# Multiplexer_Circuits.net
KiCad netlist of a schematic drawn in EAGLE
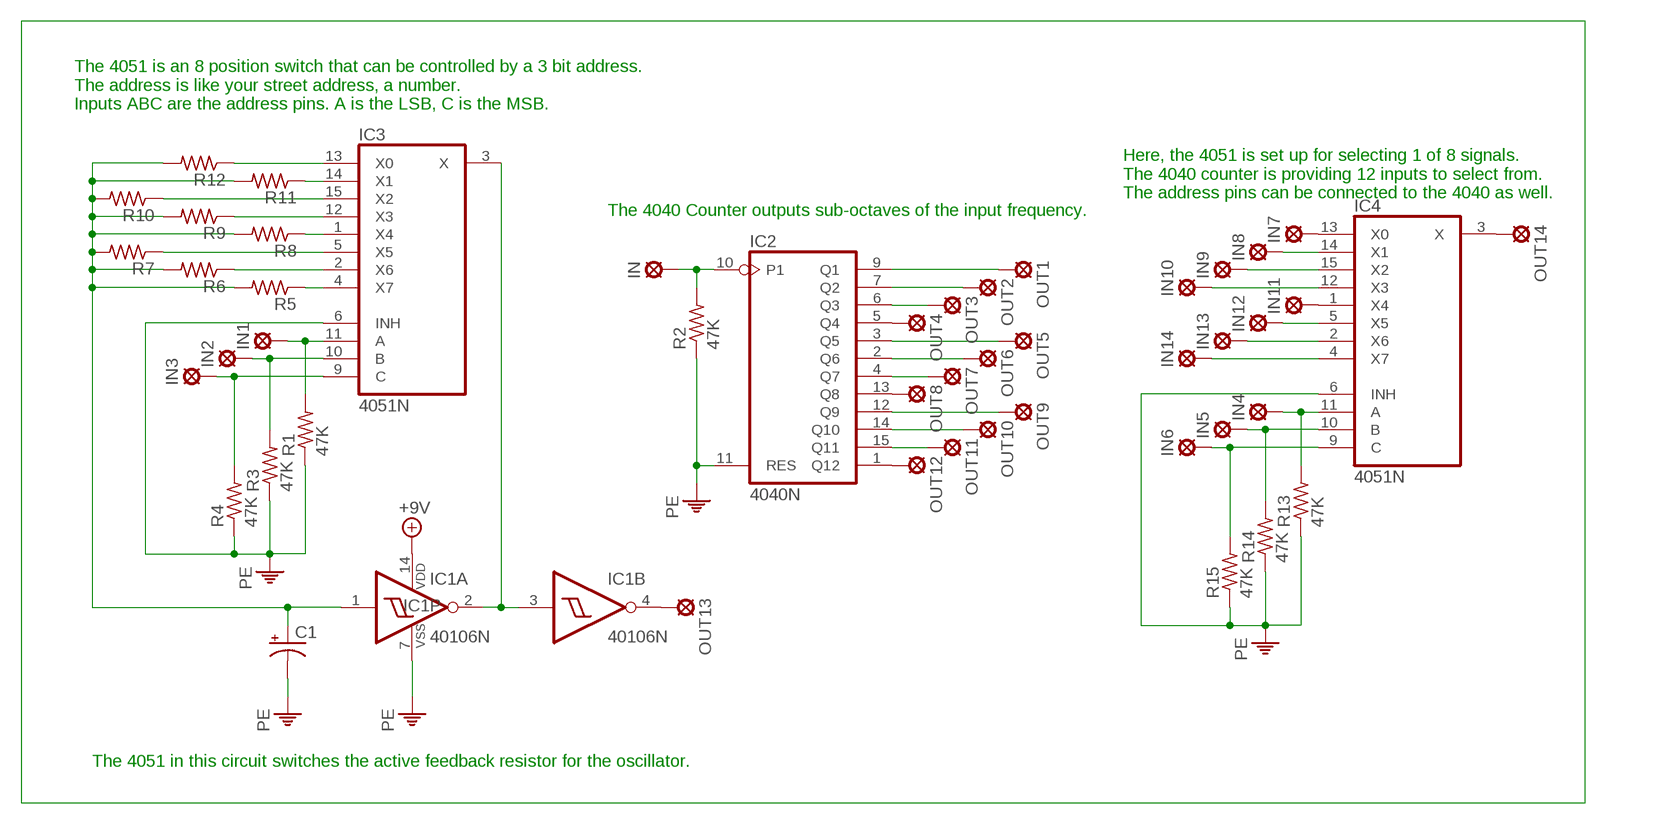
[diagram p0: schematic, sheet 1]

(export (version "E")
  (design (tool "Eeschema 10.0.6"))
  (components
    (comp (ref "C1")
      (value "CPOL-USE2,5-6E")
      (footprint "eagle-import:E2,5-6E")
      (libsource (lib "eagle-import") (part "CPOL-USE2,5-6E"))
    )
    (comp (ref "IC1")
      (value "40106N")
      (footprint "eagle-import:DIL14")
      (libsource (lib "eagle-import") (part "40106N"))
    )
    (comp (ref "IC2")
      (value "4040N")
      (footprint "eagle-import:DIL16")
      (libsource (lib "eagle-import") (part "4040N"))
    )
    (comp (ref "IC3")
      (value "4051N")
      (footprint "eagle-import:DIL16")
      (libsource (lib "eagle-import") (part "4051N"))
    )
    (comp (ref "IC4")
      (value "4051N")
      (footprint "eagle-import:DIL16")
      (libsource (lib "eagle-import") (part "4051N"))
    )
    (comp (ref "IN")
      (value "MCS10B")
      (footprint "eagle-import:MCS10B")
      (libsource (lib "eagle-import") (part "MCS10B"))
    )
    (comp (ref "IN1")
      (value "MCS10B")
      (footprint "eagle-import:MCS10B")
      (libsource (lib "eagle-import") (part "MCS10B"))
    )
    (comp (ref "IN2")
      (value "MCS10B")
      (footprint "eagle-import:MCS10B")
      (libsource (lib "eagle-import") (part "MCS10B"))
    )
    (comp (ref "IN3")
      (value "MCS10B")
      (footprint "eagle-import:MCS10B")
      (libsource (lib "eagle-import") (part "MCS10B"))
    )
    (comp (ref "IN4")
      (value "MCS10B")
      (footprint "eagle-import:MCS10B")
      (libsource (lib "eagle-import") (part "MCS10B"))
    )
    (comp (ref "IN5")
      (value "MCS10B")
      (footprint "eagle-import:MCS10B")
      (libsource (lib "eagle-import") (part "MCS10B"))
    )
    (comp (ref "IN6")
      (value "MCS10B")
      (footprint "eagle-import:MCS10B")
      (libsource (lib "eagle-import") (part "MCS10B"))
    )
    (comp (ref "IN7")
      (value "MCS10B")
      (footprint "eagle-import:MCS10B")
      (libsource (lib "eagle-import") (part "MCS10B"))
    )
    (comp (ref "IN8")
      (value "MCS10B")
      (footprint "eagle-import:MCS10B")
      (libsource (lib "eagle-import") (part "MCS10B"))
    )
    (comp (ref "IN9")
      (value "MCS10B")
      (footprint "eagle-import:MCS10B")
      (libsource (lib "eagle-import") (part "MCS10B"))
    )
    (comp (ref "IN10")
      (value "MCS10B")
      (footprint "eagle-import:MCS10B")
      (libsource (lib "eagle-import") (part "MCS10B"))
    )
    (comp (ref "IN11")
      (value "MCS10B")
      (footprint "eagle-import:MCS10B")
      (libsource (lib "eagle-import") (part "MCS10B"))
    )
    (comp (ref "IN12")
      (value "MCS10B")
      (footprint "eagle-import:MCS10B")
      (libsource (lib "eagle-import") (part "MCS10B"))
    )
    (comp (ref "IN13")
      (value "MCS10B")
      (footprint "eagle-import:MCS10B")
      (libsource (lib "eagle-import") (part "MCS10B"))
    )
    (comp (ref "IN14")
      (value "MCS10B")
      (footprint "eagle-import:MCS10B")
      (libsource (lib "eagle-import") (part "MCS10B"))
    )
    (comp (ref "OUT1")
      (value "MCS10B")
      (footprint "eagle-import:MCS10B")
      (libsource (lib "eagle-import") (part "MCS10B"))
    )
    (comp (ref "OUT2")
      (value "MCS10B")
      (footprint "eagle-import:MCS10B")
      (libsource (lib "eagle-import") (part "MCS10B"))
    )
    (comp (ref "OUT3")
      (value "MCS10B")
      (footprint "eagle-import:MCS10B")
      (libsource (lib "eagle-import") (part "MCS10B"))
    )
    (comp (ref "OUT4")
      (value "MCS10B")
      (footprint "eagle-import:MCS10B")
      (libsource (lib "eagle-import") (part "MCS10B"))
    )
    (comp (ref "OUT5")
      (value "MCS10B")
      (footprint "eagle-import:MCS10B")
      (libsource (lib "eagle-import") (part "MCS10B"))
    )
    (comp (ref "OUT6")
      (value "MCS10B")
      (footprint "eagle-import:MCS10B")
      (libsource (lib "eagle-import") (part "MCS10B"))
    )
    (comp (ref "OUT7")
      (value "MCS10B")
      (footprint "eagle-import:MCS10B")
      (libsource (lib "eagle-import") (part "MCS10B"))
    )
    (comp (ref "OUT8")
      (value "MCS10B")
      (footprint "eagle-import:MCS10B")
      (libsource (lib "eagle-import") (part "MCS10B"))
    )
    (comp (ref "OUT9")
      (value "MCS10B")
      (footprint "eagle-import:MCS10B")
      (libsource (lib "eagle-import") (part "MCS10B"))
    )
    (comp (ref "OUT10")
      (value "MCS10B")
      (footprint "eagle-import:MCS10B")
      (libsource (lib "eagle-import") (part "MCS10B"))
    )
    (comp (ref "OUT11")
      (value "MCS10B")
      (footprint "eagle-import:MCS10B")
      (libsource (lib "eagle-import") (part "MCS10B"))
    )
    (comp (ref "OUT12")
      (value "MCS10B")
      (footprint "eagle-import:MCS10B")
      (libsource (lib "eagle-import") (part "MCS10B"))
    )
    (comp (ref "OUT13")
      (value "MCS10B")
      (footprint "eagle-import:MCS10B")
      (libsource (lib "eagle-import") (part "MCS10B"))
    )
    (comp (ref "OUT14")
      (value "MCS10B")
      (footprint "eagle-import:MCS10B")
      (libsource (lib "eagle-import") (part "MCS10B"))
    )
    (comp (ref "R1")
      (value "47K")
      (footprint "eagle-import:0204_7")
      (libsource (lib "eagle-import") (part "R-US_0204/7"))
    )
    (comp (ref "R2")
      (value "47K")
      (footprint "eagle-import:0204_7")
      (libsource (lib "eagle-import") (part "R-US_0204/7"))
    )
    (comp (ref "R3")
      (value "47K")
      (footprint "eagle-import:0204_7")
      (libsource (lib "eagle-import") (part "R-US_0204/7"))
    )
    (comp (ref "R4")
      (value "47K")
      (footprint "eagle-import:0204_7")
      (libsource (lib "eagle-import") (part "R-US_0204/7"))
    )
    (comp (ref "R5")
      (value "R-US_0204/7")
      (footprint "eagle-import:0204_7")
      (libsource (lib "eagle-import") (part "R-US_0204/7"))
    )
    (comp (ref "R6")
      (value "R-US_0204/7")
      (footprint "eagle-import:0204_7")
      (libsource (lib "eagle-import") (part "R-US_0204/7"))
    )
    (comp (ref "R7")
      (value "R-US_0204/7")
      (footprint "eagle-import:0204_7")
      (libsource (lib "eagle-import") (part "R-US_0204/7"))
    )
    (comp (ref "R8")
      (value "R-US_0204/7")
      (footprint "eagle-import:0204_7")
      (libsource (lib "eagle-import") (part "R-US_0204/7"))
    )
    (comp (ref "R9")
      (value "R-US_0204/7")
      (footprint "eagle-import:0204_7")
      (libsource (lib "eagle-import") (part "R-US_0204/7"))
    )
    (comp (ref "R10")
      (value "R-US_0204/7")
      (footprint "eagle-import:0204_7")
      (libsource (lib "eagle-import") (part "R-US_0204/7"))
    )
    (comp (ref "R11")
      (value "R-US_0204/7")
      (footprint "eagle-import:0204_7")
      (libsource (lib "eagle-import") (part "R-US_0204/7"))
    )
    (comp (ref "R12")
      (value "R-US_0204/7")
      (footprint "eagle-import:0204_7")
      (libsource (lib "eagle-import") (part "R-US_0204/7"))
    )
    (comp (ref "R13")
      (value "47K")
      (footprint "eagle-import:0204_7")
      (libsource (lib "eagle-import") (part "R-US_0204/7"))
    )
    (comp (ref "R14")
      (value "47K")
      (footprint "eagle-import:0204_7")
      (libsource (lib "eagle-import") (part "R-US_0204/7"))
    )
    (comp (ref "R15")
      (value "47K")
      (footprint "eagle-import:0204_7")
      (libsource (lib "eagle-import") (part "R-US_0204/7"))
    )
  )
  (nets
    (net (code "1") (name "+9V") (class "Default")
      (node (ref "IC1") (pin "14") (pinfunction "VDD_14") (pintype "power_in"))
    )
    (net (code "2") (name "Net-(IC1A-I)") (class "Default")
      (node (ref "C1") (pin "+") (pinfunction "+_+") (pintype "passive"))
      (node (ref "IC1") (pin "1") (pinfunction "I_1") (pintype "input"))
      (node (ref "R10") (pin "2") (pinfunction "2_2") (pintype "passive"))
      (node (ref "R11") (pin "2") (pinfunction "2_2") (pintype "passive"))
      (node (ref "R12") (pin "2") (pinfunction "2_2") (pintype "passive"))
      (node (ref "R5") (pin "2") (pinfunction "2_2") (pintype "passive"))
      (node (ref "R6") (pin "2") (pinfunction "2_2") (pintype "passive"))
      (node (ref "R7") (pin "2") (pinfunction "2_2") (pintype "passive"))
      (node (ref "R8") (pin "2") (pinfunction "2_2") (pintype "passive"))
      (node (ref "R9") (pin "2") (pinfunction "2_2") (pintype "passive"))
    )
    (net (code "3") (name "Net-(IC1A-O)") (class "Default")
      (node (ref "IC1") (pin "2") (pinfunction "O_2") (pintype "output"))
      (node (ref "IC1") (pin "3") (pinfunction "I_3") (pintype "input"))
      (node (ref "IC3") (pin "3") (pinfunction "X_3") (pintype "bidirectional"))
    )
    (net (code "4") (name "Net-(IC1B-O)") (class "Default")
      (node (ref "IC1") (pin "4") (pinfunction "O_4") (pintype "output"))
      (node (ref "OUT13") (pin "MP") (pinfunction "MP_MP") (pintype "passive"))
    )
    (net (code "5") (name "Net-(IC2A-P1)") (class "Default")
      (node (ref "IC2") (pin "10") (pinfunction "P1_10") (pintype "input"))
      (node (ref "IN") (pin "MP") (pinfunction "MP_MP") (pintype "passive"))
      (node (ref "R2") (pin "2") (pinfunction "2_2") (pintype "passive"))
    )
    (net (code "6") (name "Net-(IC2A-Q1)") (class "Default")
      (node (ref "IC2") (pin "9") (pinfunction "Q1_9") (pintype "output"))
      (node (ref "OUT1") (pin "MP") (pinfunction "MP_MP") (pintype "passive"))
    )
    (net (code "7") (name "Net-(IC2A-Q2)") (class "Default")
      (node (ref "IC2") (pin "7") (pinfunction "Q2_7") (pintype "output"))
      (node (ref "OUT2") (pin "MP") (pinfunction "MP_MP") (pintype "passive"))
    )
    (net (code "8") (name "Net-(IC2A-Q3)") (class "Default")
      (node (ref "IC2") (pin "6") (pinfunction "Q3_6") (pintype "output"))
      (node (ref "OUT3") (pin "MP") (pinfunction "MP_MP") (pintype "passive"))
    )
    (net (code "9") (name "Net-(IC2A-Q4)") (class "Default")
      (node (ref "IC2") (pin "5") (pinfunction "Q4_5") (pintype "output"))
      (node (ref "OUT4") (pin "MP") (pinfunction "MP_MP") (pintype "passive"))
    )
    (net (code "10") (name "Net-(IC2A-Q5)") (class "Default")
      (node (ref "IC2") (pin "3") (pinfunction "Q5_3") (pintype "output"))
      (node (ref "OUT5") (pin "MP") (pinfunction "MP_MP") (pintype "passive"))
    )
    (net (code "11") (name "Net-(IC2A-Q6)") (class "Default")
      (node (ref "IC2") (pin "2") (pinfunction "Q6_2") (pintype "output"))
      (node (ref "OUT6") (pin "MP") (pinfunction "MP_MP") (pintype "passive"))
    )
    (net (code "12") (name "Net-(IC2A-Q7)") (class "Default")
      (node (ref "IC2") (pin "4") (pinfunction "Q7_4") (pintype "output"))
      (node (ref "OUT7") (pin "MP") (pinfunction "MP_MP") (pintype "passive"))
    )
    (net (code "13") (name "Net-(IC2A-Q8)") (class "Default")
      (node (ref "IC2") (pin "13") (pinfunction "Q8_13") (pintype "output"))
      (node (ref "OUT8") (pin "MP") (pinfunction "MP_MP") (pintype "passive"))
    )
    (net (code "14") (name "Net-(IC2A-Q9)") (class "Default")
      (node (ref "IC2") (pin "12") (pinfunction "Q9_12") (pintype "output"))
      (node (ref "OUT9") (pin "MP") (pinfunction "MP_MP") (pintype "passive"))
    )
    (net (code "15") (name "Net-(IC2A-Q10)") (class "Default")
      (node (ref "IC2") (pin "14") (pinfunction "Q10_14") (pintype "output"))
      (node (ref "OUT10") (pin "MP") (pinfunction "MP_MP") (pintype "passive"))
    )
    (net (code "16") (name "Net-(IC2A-Q11)") (class "Default")
      (node (ref "IC2") (pin "15") (pinfunction "Q11_15") (pintype "output"))
      (node (ref "OUT11") (pin "MP") (pinfunction "MP_MP") (pintype "passive"))
    )
    (net (code "17") (name "Net-(IC2A-Q12)") (class "Default")
      (node (ref "IC2") (pin "1") (pinfunction "Q12_1") (pintype "output"))
      (node (ref "OUT12") (pin "MP") (pinfunction "MP_MP") (pintype "passive"))
    )
    (net (code "18") (name "Net-(IC3A-A)") (class "Default")
      (node (ref "IC3") (pin "11") (pinfunction "A_11") (pintype "input"))
      (node (ref "IN1") (pin "MP") (pinfunction "MP_MP") (pintype "passive"))
      (node (ref "R1") (pin "2") (pinfunction "2_2") (pintype "passive"))
    )
    (net (code "19") (name "Net-(IC3A-B)") (class "Default")
      (node (ref "IC3") (pin "10") (pinfunction "B_10") (pintype "input"))
      (node (ref "IN2") (pin "MP") (pinfunction "MP_MP") (pintype "passive"))
      (node (ref "R3") (pin "2") (pinfunction "2_2") (pintype "passive"))
    )
    (net (code "20") (name "Net-(IC3A-C)") (class "Default")
      (node (ref "IC3") (pin "9") (pinfunction "C_9") (pintype "input"))
      (node (ref "IN3") (pin "MP") (pinfunction "MP_MP") (pintype "passive"))
      (node (ref "R4") (pin "2") (pinfunction "2_2") (pintype "passive"))
    )
    (net (code "21") (name "Net-(IC3A-X0)") (class "Default")
      (node (ref "IC3") (pin "13") (pinfunction "X0_13") (pintype "bidirectional"))
      (node (ref "R12") (pin "1") (pinfunction "1_1") (pintype "passive"))
    )
    (net (code "22") (name "Net-(IC3A-X1)") (class "Default")
      (node (ref "IC3") (pin "14") (pinfunction "X1_14") (pintype "bidirectional"))
      (node (ref "R11") (pin "1") (pinfunction "1_1") (pintype "passive"))
    )
    (net (code "23") (name "Net-(IC3A-X2)") (class "Default")
      (node (ref "IC3") (pin "15") (pinfunction "X2_15") (pintype "bidirectional"))
      (node (ref "R10") (pin "1") (pinfunction "1_1") (pintype "passive"))
    )
    (net (code "24") (name "Net-(IC3A-X3)") (class "Default")
      (node (ref "IC3") (pin "12") (pinfunction "X3_12") (pintype "bidirectional"))
      (node (ref "R9") (pin "1") (pinfunction "1_1") (pintype "passive"))
    )
    (net (code "25") (name "Net-(IC3A-X4)") (class "Default")
      (node (ref "IC3") (pin "1") (pinfunction "X4_1") (pintype "bidirectional"))
      (node (ref "R8") (pin "1") (pinfunction "1_1") (pintype "passive"))
    )
    (net (code "26") (name "Net-(IC3A-X5)") (class "Default")
      (node (ref "IC3") (pin "5") (pinfunction "X5_5") (pintype "bidirectional"))
      (node (ref "R7") (pin "1") (pinfunction "1_1") (pintype "passive"))
    )
    (net (code "27") (name "Net-(IC3A-X6)") (class "Default")
      (node (ref "IC3") (pin "2") (pinfunction "X6_2") (pintype "bidirectional"))
      (node (ref "R6") (pin "1") (pinfunction "1_1") (pintype "passive"))
    )
    (net (code "28") (name "Net-(IC3A-X7)") (class "Default")
      (node (ref "IC3") (pin "4") (pinfunction "X7_4") (pintype "bidirectional"))
      (node (ref "R5") (pin "1") (pinfunction "1_1") (pintype "passive"))
    )
    (net (code "29") (name "Net-(IC4A-A)") (class "Default")
      (node (ref "IC4") (pin "11") (pinfunction "A_11") (pintype "input"))
      (node (ref "IN4") (pin "MP") (pinfunction "MP_MP") (pintype "passive"))
      (node (ref "R13") (pin "2") (pinfunction "2_2") (pintype "passive"))
    )
    (net (code "30") (name "Net-(IC4A-B)") (class "Default")
      (node (ref "IC4") (pin "10") (pinfunction "B_10") (pintype "input"))
      (node (ref "IN5") (pin "MP") (pinfunction "MP_MP") (pintype "passive"))
      (node (ref "R14") (pin "2") (pinfunction "2_2") (pintype "passive"))
    )
    (net (code "31") (name "Net-(IC4A-C)") (class "Default")
      (node (ref "IC4") (pin "9") (pinfunction "C_9") (pintype "input"))
      (node (ref "IN6") (pin "MP") (pinfunction "MP_MP") (pintype "passive"))
      (node (ref "R15") (pin "2") (pinfunction "2_2") (pintype "passive"))
    )
    (net (code "32") (name "Net-(IC4A-X)") (class "Default")
      (node (ref "IC4") (pin "3") (pinfunction "X_3") (pintype "bidirectional"))
      (node (ref "OUT14") (pin "MP") (pinfunction "MP_MP") (pintype "passive"))
    )
    (net (code "33") (name "Net-(IC4A-X0)") (class "Default")
      (node (ref "IC4") (pin "13") (pinfunction "X0_13") (pintype "bidirectional"))
      (node (ref "IN7") (pin "MP") (pinfunction "MP_MP") (pintype "passive"))
    )
    (net (code "34") (name "Net-(IC4A-X1)") (class "Default")
      (node (ref "IC4") (pin "14") (pinfunction "X1_14") (pintype "bidirectional"))
      (node (ref "IN8") (pin "MP") (pinfunction "MP_MP") (pintype "passive"))
    )
    (net (code "35") (name "Net-(IC4A-X2)") (class "Default")
      (node (ref "IC4") (pin "15") (pinfunction "X2_15") (pintype "bidirectional"))
      (node (ref "IN9") (pin "MP") (pinfunction "MP_MP") (pintype "passive"))
    )
    (net (code "36") (name "Net-(IC4A-X3)") (class "Default")
      (node (ref "IC4") (pin "12") (pinfunction "X3_12") (pintype "bidirectional"))
      (node (ref "IN10") (pin "MP") (pinfunction "MP_MP") (pintype "passive"))
    )
    (net (code "37") (name "Net-(IC4A-X4)") (class "Default")
      (node (ref "IC4") (pin "1") (pinfunction "X4_1") (pintype "bidirectional"))
      (node (ref "IN11") (pin "MP") (pinfunction "MP_MP") (pintype "passive"))
    )
    (net (code "38") (name "Net-(IC4A-X5)") (class "Default")
      (node (ref "IC4") (pin "5") (pinfunction "X5_5") (pintype "bidirectional"))
      (node (ref "IN12") (pin "MP") (pinfunction "MP_MP") (pintype "passive"))
    )
    (net (code "39") (name "Net-(IC4A-X6)") (class "Default")
      (node (ref "IC4") (pin "2") (pinfunction "X6_2") (pintype "bidirectional"))
      (node (ref "IN13") (pin "MP") (pinfunction "MP_MP") (pintype "passive"))
    )
    (net (code "40") (name "Net-(IC4A-X7)") (class "Default")
      (node (ref "IC4") (pin "4") (pinfunction "X7_4") (pintype "bidirectional"))
      (node (ref "IN14") (pin "MP") (pinfunction "MP_MP") (pintype "passive"))
    )
    (net (code "41") (name "PE") (class "Default")
      (node (ref "C1") (pin "-") (pinfunction "-_-") (pintype "passive"))
      (node (ref "IC1") (pin "7") (pinfunction "VSS_7") (pintype "power_in"))
      (node (ref "IC2") (pin "11") (pinfunction "RES_11") (pintype "input"))
      (node (ref "IC3") (pin "6") (pinfunction "INH_6") (pintype "input"))
      (node (ref "IC4") (pin "6") (pinfunction "INH_6") (pintype "input"))
      (node (ref "R1") (pin "1") (pinfunction "1_1") (pintype "passive"))
      (node (ref "R13") (pin "1") (pinfunction "1_1") (pintype "passive"))
      (node (ref "R14") (pin "1") (pinfunction "1_1") (pintype "passive"))
      (node (ref "R15") (pin "1") (pinfunction "1_1") (pintype "passive"))
      (node (ref "R2") (pin "1") (pinfunction "1_1") (pintype "passive"))
      (node (ref "R3") (pin "1") (pinfunction "1_1") (pintype "passive"))
      (node (ref "R4") (pin "1") (pinfunction "1_1") (pintype "passive"))
    )
  )
)
